# 24V_Conv_Draft.net
KiCad netlist of a schematic drawn in Altium Designer
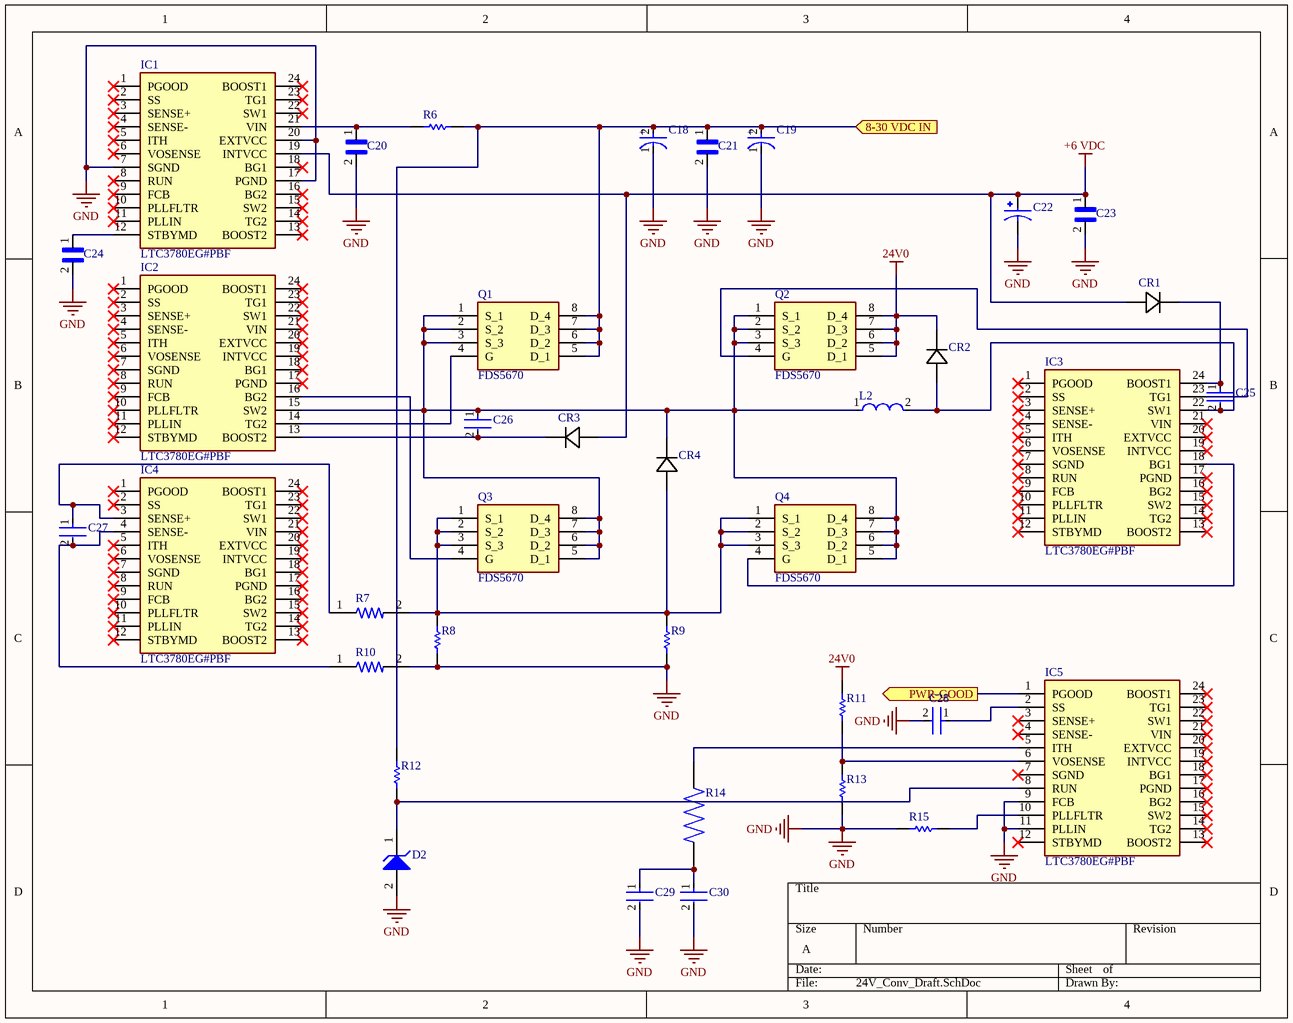
[diagram p0: 24V_Conv_Draft.SchDoc]

(export (version "E")
  (design (tool "Eeschema 10.0.6"))
  (components
    (comp (ref "C18")
      (value "35SVPF22M")
      (footprint "FP-SVPFC6-MFG")
      (description "CAP ALUM POLY 22UF 20% 35V SMD")
      (fields (field (name "TOLERANCE") "20%") (field (name "VOLTAGE") "35V"))
      (libsource (lib "Altium Content Vault") (part "203bc49f2ac43e59fd269a8c329ed05"))
    )
    (comp (ref "C19")
      (value "EEE-HA1E221UP")
      (footprint "FP-HAF-MFG")
      (description "CAP ALUM 220UF 20% 25V SMD")
      (fields
        (field (name "VOLTAGE") "25V")
        (field (name "OCTOPART") "https://octopart.com/eee-ha1e221up-panasonic-39481261")
      )
      (libsource (lib "Altium Content Vault") (part "a00bbbee19879c290e62620ae7e47b1"))
    )
    (comp (ref "C20")
      (value "GRM022R60J104ME15L")
      (footprint "CAPC0402X22N")
      (description "01005 0.1 uF 6.3 V Â±20% Tolerance X5R SMT Multilayer Ceramic Capacitor")
      (fields (field (name "MF") "Murata Electronics"))
      (libsource (lib "0.1uF_Cap_GRM022R60J104ME15L") (part "GRM022R60J104ME15L"))
    )
    (comp (ref "C21")
      (value "GRM022R60J104ME15L")
      (footprint "CAPC0402X22N")
      (description "01005 0.1 uF 6.3 V Â±20% Tolerance X5R SMT Multilayer Ceramic Capacitor")
      (fields (field (name "MF") "Murata Electronics"))
      (libsource (lib "0.1uF_Cap_GRM022R60J104ME15L") (part "GRM022R60J104ME15L"))
    )
    (comp (ref "C22")
      (value "EEVEB2V4R7Q")
      (footprint "CAP_EEVEB2V4R7Q")
      (description "CAP ALUM 4.7UF 20% 350V SMD")
      (fields (field (name "MF") "Panasonic Electronic Components") (field (name "MP") "EEV-EB2V4R7Q"))
      (libsource (lib "4.7uF_Pol_Cap_EEVEB2V4R7Q") (part "EEVEB2V4R7Q"))
    )
    (comp (ref "C23")
      (value "GRM022R60J104ME15L")
      (footprint "CAPC0402X22N")
      (description "01005 0.1 uF 6.3 V Â±20% Tolerance X5R SMT Multilayer Ceramic Capacitor")
      (fields (field (name "MF") "Murata Electronics"))
      (libsource (lib "0.1uF_Cap_GRM022R60J104ME15L") (part "GRM022R60J104ME15L"))
    )
    (comp (ref "C24")
      (value "GRM022R60J104ME15L")
      (footprint "CAPC0402X22N")
      (description "01005 0.1 uF 6.3 V Â±20% Tolerance X5R SMT Multilayer Ceramic Capacitor")
      (fields (field (name "MF") "Murata Electronics"))
      (libsource (lib "0.1uF_Cap_GRM022R60J104ME15L") (part "GRM022R60J104ME15L"))
    )
    (comp (ref "C25")
      (value "C0805C224K5RACTU")
      (footprint "FP-C0805C-DN-IPC_A")
      (description "CAP CER 0.22UF 50V X7R 0805")
      (fields
        (field (name "MANUFACTURER") "KEMET")
        (field (name "OCTOPART") "https://octopart.com/c0805c224k5ractu-kemet-144670")
      )
      (libsource (lib "Altium Content Vault") (part "b4654b650e69147ec39a6b967a45e02"))
    )
    (comp (ref "C26")
      (value "C0805C224K5RACTU")
      (footprint "FP-C0805C-DN-IPC_A")
      (description "CAP CER 0.22UF 50V X7R 0805")
      (fields
        (field (name "MANUFACTURER") "KEMET")
        (field (name "OCTOPART") "https://octopart.com/c0805c224k5ractu-kemet-144670")
      )
      (libsource (lib "Altium Content Vault") (part "b4654b650e69147ec39a6b967a45e02"))
    )
    (comp (ref "C27")
      (value "C1206C680J5GACTU")
      (footprint "FP-C1206C-EB-MFG")
      (description "1206 C 68pF Ceramic Multilayer Capacitor; 50 VDC; +125degC; C0G Dielec; +/-5%")
      (fields
        (field (name "OCTOPART") "https://octopart.com/c1206c680j5gactu-kemet-138975")
        (field (name "TOLERANCE") "0.05")
      )
      (libsource (lib "Altium Content Vault") (part "b4654b650e69147ec39a6b967a45e02"))
    )
    (comp (ref "C28")
      (value "CC0805KRX7R9BB223")
      (footprint "FP-CC0805-0_85-IPC_C")
      (description "CAP CER 0.022UF 50V X7R 0805")
      (fields
        (field (name "OCTOPART") "https://octopart.com/cc0805krx7r9bb223-yageo-39467761")
        (field (name "MANUFACTURER") "Yageo")
      )
      (libsource (lib "Altium Content Vault") (part "11868f565c42a9108669ba33697ecf6"))
    )
    (comp (ref "C29")
      (value "C1206C470J5GACTU")
      (footprint "FP-C1206C-EB-MFG")
      (description "CAP CER 47PF 50V C0G/NP0 1206")
      (fields
        (field (name "TOLERANCE") "0.05")
        (field (name "OCTOPART") "https://octopart.com/c1206c470j5gactu-kemet-96509")
      )
      (libsource (lib "Altium Content Vault") (part "b4654b650e69147ec39a6b967a45e02"))
    )
    (comp (ref "C30")
      (value "CC0603KRX7R9BB103")
      (footprint "FP-CC0603-DA-IPC_B")
      (description "CAP CER 10000PF 50V X7R 0603")
      (fields (field (name "TOLERANCE") "0.1") (field (name "MANUFACTURER") "YAGEO"))
      (libsource (lib "Altium Content Vault") (part "11868f565c42a9108669ba33697ecf6"))
    )
    (comp (ref "CR1")
      (value "SS34-E3/9AT")
      (footprint "CR_3/9AT_VIS")
      (description "No Description Available")
      (fields (field (name "COPYRIGHT") "Copyright (C) 2021 Ultra Librarian. All rights reserved."))
      (libsource (lib "SS34-E3&slash_9AT") (part "SS34-E3/9AT"))
    )
    (comp (ref "CR2")
      (value "SS34-E3/9AT")
      (footprint "CR_3/9AT_VIS")
      (description "No Description Available")
      (fields (field (name "COPYRIGHT") "Copyright (C) 2021 Ultra Librarian. All rights reserved."))
      (libsource (lib "SS34-E3&slash_9AT") (part "SS34-E3/9AT"))
    )
    (comp (ref "CR3")
      (value "SS34-E3/9AT")
      (footprint "CR_3/9AT_VIS")
      (description "No Description Available")
      (fields (field (name "COPYRIGHT") "Copyright (C) 2021 Ultra Librarian. All rights reserved."))
      (libsource (lib "SS34-E3&slash_9AT") (part "SS34-E3/9AT"))
    )
    (comp (ref "CR4")
      (value "SS34-E3/9AT")
      (footprint "CR_3/9AT_VIS")
      (description "No Description Available")
      (fields (field (name "COPYRIGHT") "Copyright (C) 2021 Ultra Librarian. All rights reserved."))
      (libsource (lib "SS34-E3&slash_9AT") (part "SS34-E3/9AT"))
    )
    (comp (ref "D2")
      (value "MMSZ4689T1G")
      (footprint "ONSC-SOD-123-2-425-04_V")
      (description "Zener Voltage Regulator, 500 mW, 2-Pin SOD-123, Pb-Free, Tape and Reel")
      (fields (field (name "MANUFACTURER") "On Semiconductor"))
      (libsource (lib "Altium Content Vault") (part "ONSC-K1A2-2"))
    )
    (comp (ref "IC1")
      (value "LTC3780EG#PBF")
      (footprint "SOP65P780X200-24N")
      (description "Integrated Circuit")
      (fields (field (name "MOUSER PART NUMBER") "584-LTC3780EG#PBF"))
      (libsource (lib "SamacSys") (part "LTC3780EG#PBF"))
    )
    (comp (ref "IC2")
      (value "LTC3780EG#PBF")
      (footprint "SOP65P780X200-24N")
      (description "Integrated Circuit")
      (fields (field (name "MOUSER PART NUMBER") "584-LTC3780EG#PBF"))
      (libsource (lib "SamacSys") (part "LTC3780EG#PBF"))
    )
    (comp (ref "IC3")
      (value "LTC3780EG#PBF")
      (footprint "SOP65P780X200-24N")
      (description "Integrated Circuit")
      (fields (field (name "MOUSER PART NUMBER") "584-LTC3780EG#PBF"))
      (libsource (lib "SamacSys") (part "LTC3780EG#PBF"))
    )
    (comp (ref "IC4")
      (value "LTC3780EG#PBF")
      (footprint "SOP65P780X200-24N")
      (description "Integrated Circuit")
      (fields (field (name "MOUSER PART NUMBER") "584-LTC3780EG#PBF"))
      (libsource (lib "SamacSys") (part "LTC3780EG#PBF"))
    )
    (comp (ref "IC5")
      (value "LTC3780EG#PBF")
      (footprint "SOP65P780X200-24N")
      (description "Integrated Circuit")
      (fields (field (name "MOUSER PART NUMBER") "584-LTC3780EG#PBF"))
      (libsource (lib "SamacSys") (part "LTC3780EG#PBF"))
    )
    (comp (ref "L2")
      (value "IHLP5050CEER4R7M01")
      (footprint "FP-IHLP-5050CE-FP_3_175x3-MFG")
      (description "Commercial Inductors, High Saturation Series 4.7uH 10A 15mΩ 20%")
      (fields (field (name "TOLERANCE") "20%"))
      (libsource (lib "Altium Content Vault") (part "725321dda6339637d4d059423bc1c3c"))
    )
    (comp (ref "Q1")
      (value "FDS5670")
      (footprint "SOIC127P600X175-8N")
      (description "MOSFET (N-Channel)")
      (fields (field (name "MOUSER PART NUMBER") "512-FDS5670"))
      (libsource (lib "SamacSys") (part "FDS5670"))
    )
    (comp (ref "Q2")
      (value "FDS5670")
      (footprint "SOIC127P600X175-8N")
      (description "MOSFET (N-Channel)")
      (fields (field (name "MOUSER PART NUMBER") "512-FDS5670"))
      (libsource (lib "SamacSys") (part "FDS5670"))
    )
    (comp (ref "Q3")
      (value "FDS5670")
      (footprint "SOIC127P600X175-8N")
      (description "MOSFET (N-Channel)")
      (fields (field (name "MOUSER PART NUMBER") "512-FDS5670"))
      (libsource (lib "SamacSys") (part "FDS5670"))
    )
    (comp (ref "Q4")
      (value "FDS5670")
      (footprint "SOIC127P600X175-8N")
      (description "MOSFET (N-Channel)")
      (fields (field (name "MOUSER PART NUMBER") "512-FDS5670"))
      (libsource (lib "SamacSys") (part "FDS5670"))
    )
    (comp (ref "R6")
      (value "ERJ-6ENF10R0V")
      (footprint "RESC2013X70X40NL20T20")
      (fields (field (name "MANUFACTURER") "Panasonic"))
      (libsource (lib "Altium Content Vault") (part "RES"))
    )
    (comp (ref "R7")
      (value "CRGS0805J100R")
      (footprint "RESC2012X65N")
      (description "100 Ohms Â±5% 0.5W, 1/2W Chip Resistor 0805 _2012 Metric_ Pulse Withstanding Thick Film")
      (fields (field (name "MF") "TE Connectivity"))
      (libsource (lib "100_Res_CRGS0805J100R") (part "CRGS0805J100R"))
    )
    (comp (ref "R8")
      (value "ERJ8BWFR018V")
      (footprint "RESC3216X70X50NL05T20")
      (fields (field (name "MANUFACTURER") "Panasonic"))
      (libsource (lib "Altium Content Vault") (part "RES"))
    )
    (comp (ref "R9")
      (value "ERJ8BWFR018V")
      (footprint "RESC3216X70X50NL05T20")
      (fields (field (name "MANUFACTURER") "Panasonic"))
      (libsource (lib "Altium Content Vault") (part "RES"))
    )
    (comp (ref "R10")
      (value "CRGS0805J100R")
      (footprint "RESC2012X65N")
      (description "100 Ohms Â±5% 0.5W, 1/2W Chip Resistor 0805 _2012 Metric_ Pulse Withstanding Thick Film")
      (fields (field (name "MF") "TE Connectivity"))
      (libsource (lib "100_Res_CRGS0805J100R") (part "CRGS0805J100R"))
    )
    (comp (ref "R11")
      (value "CRCW1206294KFKEA")
      (footprint "RESC3216X60X45ML10T20")
      (fields (field (name "MANUFACTURER") "Vishay Dale"))
      (libsource (lib "Altium Content Vault") (part "RES"))
    )
    (comp (ref "R12")
      (value "ERJ3EKF1002V")
      (footprint "RESC1609X55X30LL15T15")
      (description "Chip Resistor, 10 KOhm, +/- 1%, 0.1 W, -55 to 155 degC, 0603 (1608 Metric), RoHS, Tape and Reel")
      (fields (field (name "TOLERANCE") "1%") (field (name "MANUFACTURER") "Panasonic"))
      (libsource (lib "Altium Content Vault") (part "RES-2"))
    )
    (comp (ref "R13")
      (value "ERJ3EKF1002V")
      (footprint "RESC1609X55X30LL15T15")
      (description "Chip Resistor, 10 KOhm, +/- 1%, 0.1 W, -55 to 155 degC, 0603 (1608 Metric), RoHS, Tape and Reel")
      (fields (field (name "TOLERANCE") "1%") (field (name "MANUFACTURER") "Panasonic"))
      (libsource (lib "Altium Content Vault") (part "RES-2"))
    )
    (comp (ref "R14")
      (value "RC1206JR-07100KL")
      (footprint "RESC3116X65N")
      (description "Carbon film resistor 100 kâ„¦ SMD 1206 0.25 W 5 % 200 ppm Yageo RC1206JR-07100KL 1 pc(s)")
      (libsource (lib "100K_Res_RC1206JR-07100KL") (part "RC1206JR-07100KL"))
    )
    (comp (ref "R15")
      (value "ERJ3EKF1002V")
      (footprint "RESC1609X55X30LL15T15")
      (description "Chip Resistor, 10 KOhm, +/- 1%, 0.1 W, -55 to 155 degC, 0603 (1608 Metric), RoHS, Tape and Reel")
      (fields (field (name "TOLERANCE") "1%") (field (name "MANUFACTURER") "Panasonic"))
      (libsource (lib "Altium Content Vault") (part "RES-2"))
    )
  )
  (nets
    (net (code "1") (name "+6 VDC") (class "Default")
      (node (ref "C22") (pin "1") (pinfunction "1_1") (pintype "passive"))
      (node (ref "C23") (pin "1") (pinfunction "1_1") (pintype "passive"))
      (node (ref "CR1") (pin "1") (pinfunction "CATHODE_1") (pintype "passive"))
      (node (ref "CR3") (pin "1") (pinfunction "CATHODE_1") (pintype "passive"))
      (node (ref "IC1") (pin "19") (pinfunction "INTVCC_19") (pintype "passive"))
    )
    (net (code "2") (name "/8-30 VDC IN") (class "Default")
      (node (ref "C18") (pin "2") (pinfunction "A_2") (pintype "passive"))
      (node (ref "C19") (pin "2") (pinfunction "A_2") (pintype "passive"))
      (node (ref "C21") (pin "1") (pinfunction "1_1") (pintype "passive"))
      (node (ref "Q1") (pin "5") (pinfunction "D_1_5") (pintype "passive"))
      (node (ref "Q1") (pin "6") (pinfunction "D_2_6") (pintype "passive"))
      (node (ref "Q1") (pin "7") (pinfunction "D_3_7") (pintype "passive"))
      (node (ref "Q1") (pin "8") (pinfunction "D_4_8") (pintype "passive"))
      (node (ref "R12") (pin "1") (pinfunction "1_1") (pintype "passive"))
      (node (ref "R6") (pin "2") (pinfunction "2_2") (pintype "passive"))
    )
    (net (code "3") (name "/PWR-GOOD") (class "Default")
      (node (ref "IC5") (pin "1") (pinfunction "PGOOD_1") (pintype "passive"))
    )
    (net (code "4") (name "24V0") (class "Default")
      (node (ref "CR2") (pin "2") (pinfunction "ANODE_2") (pintype "passive"))
      (node (ref "Q2") (pin "5") (pinfunction "D_1_5") (pintype "passive"))
      (node (ref "Q2") (pin "6") (pinfunction "D_2_6") (pintype "passive"))
      (node (ref "Q2") (pin "7") (pinfunction "D_3_7") (pintype "passive"))
      (node (ref "Q2") (pin "8") (pinfunction "D_4_8") (pintype "passive"))
      (node (ref "R11") (pin "1") (pinfunction "1_1") (pintype "passive"))
    )
    (net (code "5") (name "GND") (class "Default")
      (node (ref "C18") (pin "1") (pinfunction "C_1") (pintype "passive"))
      (node (ref "C19") (pin "1") (pinfunction "C_1") (pintype "passive"))
      (node (ref "C20") (pin "2") (pinfunction "2_2") (pintype "passive"))
      (node (ref "C21") (pin "2") (pinfunction "2_2") (pintype "passive"))
      (node (ref "C22") (pin "2") (pinfunction "2_2") (pintype "passive"))
      (node (ref "C23") (pin "2") (pinfunction "2_2") (pintype "passive"))
      (node (ref "C24") (pin "2") (pinfunction "2_2") (pintype "passive"))
      (node (ref "C28") (pin "2") (pinfunction "2_2") (pintype "passive"))
      (node (ref "C29") (pin "2") (pinfunction "2_2") (pintype "passive"))
      (node (ref "C30") (pin "2") (pinfunction "2_2") (pintype "passive"))
      (node (ref "D2") (pin "2") (pinfunction "A_2") (pintype "passive"))
      (node (ref "IC1") (pin "17") (pinfunction "PGND_17") (pintype "passive"))
      (node (ref "IC1") (pin "20") (pinfunction "EXTVCC_20") (pintype "passive"))
      (node (ref "IC1") (pin "7") (pinfunction "SGND_7") (pintype "passive"))
      (node (ref "IC5") (pin "11") (pinfunction "PLLIN_11") (pintype "passive"))
      (node (ref "IC5") (pin "9") (pinfunction "FCB_9") (pintype "passive"))
      (node (ref "R10") (pin "2") (pinfunction "2_2") (pintype "passive"))
      (node (ref "R13") (pin "2") (pinfunction "2_2") (pintype "passive"))
      (node (ref "R15") (pin "2") (pinfunction "2_2") (pintype "passive"))
      (node (ref "R8") (pin "2") (pinfunction "2_2") (pintype "passive"))
      (node (ref "R9") (pin "2") (pinfunction "2_2") (pintype "passive"))
    )
    (net (code "6") (name "Net-(C29-Pad1)") (class "Default")
      (node (ref "C29") (pin "1") (pinfunction "1_1") (pintype "passive"))
      (node (ref "C30") (pin "1") (pinfunction "1_1") (pintype "passive"))
      (node (ref "R14") (pin "2") (pinfunction "2_2") (pintype "passive"))
    )
    (net (code "7") (name "Net-(CR1-ANODE)") (class "Default")
      (node (ref "C25") (pin "1") (pinfunction "1_1") (pintype "passive"))
      (node (ref "CR1") (pin "2") (pinfunction "ANODE_2") (pintype "passive"))
      (node (ref "IC3") (pin "24") (pinfunction "BOOST1_24") (pintype "passive"))
    )
    (net (code "8") (name "Net-(CR2-CATHODE)") (class "Default")
      (node (ref "C25") (pin "2") (pinfunction "2_2") (pintype "passive"))
      (node (ref "CR2") (pin "1") (pinfunction "CATHODE_1") (pintype "passive"))
      (node (ref "IC3") (pin "22") (pinfunction "SW1_22") (pintype "passive"))
      (node (ref "L2") (pin "2") (pinfunction "2_2") (pintype "passive"))
    )
    (net (code "9") (name "Net-(CR3-ANODE)") (class "Default")
      (node (ref "C26") (pin "2") (pinfunction "2_2") (pintype "passive"))
      (node (ref "CR3") (pin "2") (pinfunction "ANODE_2") (pintype "passive"))
      (node (ref "IC2") (pin "13") (pinfunction "BOOST2_13") (pintype "passive"))
    )
    (net (code "10") (name "Net-(CR4-ANODE)") (class "Default")
      (node (ref "C26") (pin "1") (pinfunction "1_1") (pintype "passive"))
      (node (ref "CR4") (pin "2") (pinfunction "ANODE_2") (pintype "passive"))
      (node (ref "IC2") (pin "15") (pinfunction "SW2_15") (pintype "passive"))
      (node (ref "L2") (pin "1") (pinfunction "1_1") (pintype "passive"))
      (node (ref "Q1") (pin "1") (pinfunction "S_1_1") (pintype "passive"))
      (node (ref "Q1") (pin "2") (pinfunction "S_2_2") (pintype "passive"))
      (node (ref "Q1") (pin "3") (pinfunction "S_3_3") (pintype "passive"))
      (node (ref "Q2") (pin "1") (pinfunction "S_1_1") (pintype "passive"))
      (node (ref "Q2") (pin "2") (pinfunction "S_2_2") (pintype "passive"))
      (node (ref "Q2") (pin "3") (pinfunction "S_3_3") (pintype "passive"))
      (node (ref "Q3") (pin "5") (pinfunction "D_1_5") (pintype "passive"))
      (node (ref "Q3") (pin "6") (pinfunction "D_2_6") (pintype "passive"))
      (node (ref "Q3") (pin "7") (pinfunction "D_3_7") (pintype "passive"))
      (node (ref "Q3") (pin "8") (pinfunction "D_4_8") (pintype "passive"))
      (node (ref "Q4") (pin "5") (pinfunction "D_1_5") (pintype "passive"))
      (node (ref "Q4") (pin "6") (pinfunction "D_2_6") (pintype "passive"))
      (node (ref "Q4") (pin "7") (pinfunction "D_3_7") (pintype "passive"))
      (node (ref "Q4") (pin "8") (pinfunction "D_4_8") (pintype "passive"))
    )
    (net (code "11") (name "Net-(CR4-CATHODE)") (class "Default")
      (node (ref "CR4") (pin "1") (pinfunction "CATHODE_1") (pintype "passive"))
      (node (ref "Q3") (pin "1") (pinfunction "S_1_1") (pintype "passive"))
      (node (ref "Q3") (pin "2") (pinfunction "S_2_2") (pintype "passive"))
      (node (ref "Q3") (pin "3") (pinfunction "S_3_3") (pintype "passive"))
      (node (ref "Q4") (pin "1") (pinfunction "S_1_1") (pintype "passive"))
      (node (ref "Q4") (pin "2") (pinfunction "S_2_2") (pintype "passive"))
      (node (ref "Q4") (pin "3") (pinfunction "S_3_3") (pintype "passive"))
      (node (ref "R7") (pin "2") (pinfunction "2_2") (pintype "passive"))
      (node (ref "R8") (pin "1") (pinfunction "1_1") (pintype "passive"))
      (node (ref "R9") (pin "1") (pinfunction "1_1") (pintype "passive"))
    )
    (net (code "12") (name "Net-(D2-K)") (class "Default")
      (node (ref "D2") (pin "1") (pinfunction "K_1") (pintype "passive"))
      (node (ref "IC5") (pin "8") (pinfunction "RUN_8") (pintype "passive"))
      (node (ref "R12") (pin "2") (pinfunction "2_2") (pintype "passive"))
    )
    (net (code "13") (name "Net-(IC1-STBYMD)") (class "Default")
      (node (ref "C24") (pin "1") (pinfunction "1_1") (pintype "passive"))
      (node (ref "IC1") (pin "12") (pinfunction "STBYMD_12") (pintype "passive"))
    )
    (net (code "14") (name "Net-(IC1-VIN)") (class "Default")
      (node (ref "C20") (pin "1") (pinfunction "1_1") (pintype "passive"))
      (node (ref "IC1") (pin "21") (pinfunction "VIN_21") (pintype "passive"))
      (node (ref "R6") (pin "1") (pinfunction "1_1") (pintype "passive"))
    )
    (net (code "15") (name "Net-(IC2-BG2)") (class "Default")
      (node (ref "IC2") (pin "16") (pinfunction "BG2_16") (pintype "passive"))
      (node (ref "Q3") (pin "4") (pinfunction "G_4") (pintype "passive"))
    )
    (net (code "16") (name "Net-(IC2-TG2)") (class "Default")
      (node (ref "IC2") (pin "14") (pinfunction "TG2_14") (pintype "passive"))
      (node (ref "Q1") (pin "4") (pinfunction "G_4") (pintype "passive"))
    )
    (net (code "17") (name "Net-(IC3-BG1)") (class "Default")
      (node (ref "IC3") (pin "18") (pinfunction "BG1_18") (pintype "passive"))
      (node (ref "Q4") (pin "4") (pinfunction "G_4") (pintype "passive"))
    )
    (net (code "18") (name "Net-(IC3-TG1)") (class "Default")
      (node (ref "IC3") (pin "23") (pinfunction "TG1_23") (pintype "passive"))
      (node (ref "Q2") (pin "4") (pinfunction "G_4") (pintype "passive"))
    )
    (net (code "19") (name "Net-(IC4-SENSE+)") (class "Default")
      (node (ref "C27") (pin "1") (pinfunction "1_1") (pintype "passive"))
      (node (ref "IC4") (pin "3") (pinfunction "SENSE+_3") (pintype "passive"))
      (node (ref "R7") (pin "1") (pinfunction "1_1") (pintype "passive"))
    )
    (net (code "20") (name "Net-(IC4-SENSE-)") (class "Default")
      (node (ref "C27") (pin "2") (pinfunction "2_2") (pintype "passive"))
      (node (ref "IC4") (pin "4") (pinfunction "SENSE-_4") (pintype "passive"))
      (node (ref "R10") (pin "1") (pinfunction "1_1") (pintype "passive"))
    )
    (net (code "21") (name "Net-(IC5-ITH)") (class "Default")
      (node (ref "IC5") (pin "5") (pinfunction "ITH_5") (pintype "passive"))
      (node (ref "R14") (pin "1") (pinfunction "1_1") (pintype "passive"))
    )
    (net (code "22") (name "Net-(IC5-PLLFLTR)") (class "Default")
      (node (ref "IC5") (pin "10") (pinfunction "PLLFLTR_10") (pintype "passive"))
      (node (ref "R15") (pin "1") (pinfunction "1_1") (pintype "passive"))
    )
    (net (code "23") (name "Net-(IC5-SS)") (class "Default")
      (node (ref "C28") (pin "1") (pinfunction "1_1") (pintype "passive"))
      (node (ref "IC5") (pin "2") (pinfunction "SS_2") (pintype "passive"))
    )
    (net (code "24") (name "Net-(IC5-VOSENSE)") (class "Default")
      (node (ref "IC5") (pin "6") (pinfunction "VOSENSE_6") (pintype "passive"))
      (node (ref "R11") (pin "2") (pinfunction "2_2") (pintype "passive"))
      (node (ref "R13") (pin "1") (pinfunction "1_1") (pintype "passive"))
    )
    (net (code "25") (name "unconnected-(IC1-BG1-Pad18)") (class "Default")
      (node (ref "IC1") (pin "18") (pinfunction "BG1_18") (pintype "passive+no_connect"))
    )
    (net (code "26") (name "unconnected-(IC1-BG2-Pad16)") (class "Default")
      (node (ref "IC1") (pin "16") (pinfunction "BG2_16") (pintype "passive+no_connect"))
    )
    (net (code "27") (name "unconnected-(IC1-BOOST1-Pad24)") (class "Default")
      (node (ref "IC1") (pin "24") (pinfunction "BOOST1_24") (pintype "passive+no_connect"))
    )
    (net (code "28") (name "unconnected-(IC1-BOOST2-Pad13)") (class "Default")
      (node (ref "IC1") (pin "13") (pinfunction "BOOST2_13") (pintype "passive+no_connect"))
    )
    (net (code "29") (name "unconnected-(IC1-FCB-Pad9)") (class "Default")
      (node (ref "IC1") (pin "9") (pinfunction "FCB_9") (pintype "passive+no_connect"))
    )
    (net (code "30") (name "unconnected-(IC1-ITH-Pad5)") (class "Default")
      (node (ref "IC1") (pin "5") (pinfunction "ITH_5") (pintype "passive+no_connect"))
    )
    (net (code "31") (name "unconnected-(IC1-PGOOD-Pad1)") (class "Default")
      (node (ref "IC1") (pin "1") (pinfunction "PGOOD_1") (pintype "passive+no_connect"))
    )
    (net (code "32") (name "unconnected-(IC1-PLLFLTR-Pad10)") (class "Default")
      (node (ref "IC1") (pin "10") (pinfunction "PLLFLTR_10") (pintype "passive+no_connect"))
    )
    (net (code "33") (name "unconnected-(IC1-PLLIN-Pad11)") (class "Default")
      (node (ref "IC1") (pin "11") (pinfunction "PLLIN_11") (pintype "passive+no_connect"))
    )
    (net (code "34") (name "unconnected-(IC1-RUN-Pad8)") (class "Default")
      (node (ref "IC1") (pin "8") (pinfunction "RUN_8") (pintype "passive+no_connect"))
    )
    (net (code "35") (name "unconnected-(IC1-SENSE+-Pad3)") (class "Default")
      (node (ref "IC1") (pin "3") (pinfunction "SENSE+_3") (pintype "passive+no_connect"))
    )
    (net (code "36") (name "unconnected-(IC1-SENSE--Pad4)") (class "Default")
      (node (ref "IC1") (pin "4") (pinfunction "SENSE-_4") (pintype "passive+no_connect"))
    )
    (net (code "37") (name "unconnected-(IC1-SS-Pad2)") (class "Default")
      (node (ref "IC1") (pin "2") (pinfunction "SS_2") (pintype "passive+no_connect"))
    )
    (net (code "38") (name "unconnected-(IC1-SW1-Pad22)") (class "Default")
      (node (ref "IC1") (pin "22") (pinfunction "SW1_22") (pintype "passive+no_connect"))
    )
    (net (code "39") (name "unconnected-(IC1-SW2-Pad15)") (class "Default")
      (node (ref "IC1") (pin "15") (pinfunction "SW2_15") (pintype "passive+no_connect"))
    )
    (net (code "40") (name "unconnected-(IC1-TG1-Pad23)") (class "Default")
      (node (ref "IC1") (pin "23") (pinfunction "TG1_23") (pintype "passive+no_connect"))
    )
    (net (code "41") (name "unconnected-(IC1-TG2-Pad14)") (class "Default")
      (node (ref "IC1") (pin "14") (pinfunction "TG2_14") (pintype "passive+no_connect"))
    )
    (net (code "42") (name "unconnected-(IC1-VOSENSE-Pad6)") (class "Default")
      (node (ref "IC1") (pin "6") (pinfunction "VOSENSE_6") (pintype "passive+no_connect"))
    )
    (net (code "43") (name "unconnected-(IC2-BG1-Pad18)") (class "Default")
      (node (ref "IC2") (pin "18") (pinfunction "BG1_18") (pintype "passive+no_connect"))
    )
    (net (code "44") (name "unconnected-(IC2-BOOST1-Pad24)") (class "Default")
      (node (ref "IC2") (pin "24") (pinfunction "BOOST1_24") (pintype "passive+no_connect"))
    )
    (net (code "45") (name "unconnected-(IC2-EXTVCC-Pad20)") (class "Default")
      (node (ref "IC2") (pin "20") (pinfunction "EXTVCC_20") (pintype "passive+no_connect"))
    )
    (net (code "46") (name "unconnected-(IC2-FCB-Pad9)") (class "Default")
      (node (ref "IC2") (pin "9") (pinfunction "FCB_9") (pintype "passive+no_connect"))
    )
    (net (code "47") (name "unconnected-(IC2-INTVCC-Pad19)") (class "Default")
      (node (ref "IC2") (pin "19") (pinfunction "INTVCC_19") (pintype "passive+no_connect"))
    )
    (net (code "48") (name "unconnected-(IC2-ITH-Pad5)") (class "Default")
      (node (ref "IC2") (pin "5") (pinfunction "ITH_5") (pintype "passive+no_connect"))
    )
    (net (code "49") (name "unconnected-(IC2-PGND-Pad17)") (class "Default")
      (node (ref "IC2") (pin "17") (pinfunction "PGND_17") (pintype "passive+no_connect"))
    )
    (net (code "50") (name "unconnected-(IC2-PGOOD-Pad1)") (class "Default")
      (node (ref "IC2") (pin "1") (pinfunction "PGOOD_1") (pintype "passive+no_connect"))
    )
    (net (code "51") (name "unconnected-(IC2-PLLFLTR-Pad10)") (class "Default")
      (node (ref "IC2") (pin "10") (pinfunction "PLLFLTR_10") (pintype "passive+no_connect"))
    )
    (net (code "52") (name "unconnected-(IC2-PLLIN-Pad11)") (class "Default")
      (node (ref "IC2") (pin "11") (pinfunction "PLLIN_11") (pintype "passive+no_connect"))
    )
    (net (code "53") (name "unconnected-(IC2-RUN-Pad8)") (class "Default")
      (node (ref "IC2") (pin "8") (pinfunction "RUN_8") (pintype "passive+no_connect"))
    )
    (net (code "54") (name "unconnected-(IC2-SENSE+-Pad3)") (class "Default")
      (node (ref "IC2") (pin "3") (pinfunction "SENSE+_3") (pintype "passive+no_connect"))
    )
    (net (code "55") (name "unconnected-(IC2-SENSE--Pad4)") (class "Default")
      (node (ref "IC2") (pin "4") (pinfunction "SENSE-_4") (pintype "passive+no_connect"))
    )
    (net (code "56") (name "unconnected-(IC2-SGND-Pad7)") (class "Default")
      (node (ref "IC2") (pin "7") (pinfunction "SGND_7") (pintype "passive+no_connect"))
    )
    (net (code "57") (name "unconnected-(IC2-SS-Pad2)") (class "Default")
      (node (ref "IC2") (pin "2") (pinfunction "SS_2") (pintype "passive+no_connect"))
    )
    (net (code "58") (name "unconnected-(IC2-STBYMD-Pad12)") (class "Default")
      (node (ref "IC2") (pin "12") (pinfunction "STBYMD_12") (pintype "passive+no_connect"))
    )
    (net (code "59") (name "unconnected-(IC2-SW1-Pad22)") (class "Default")
      (node (ref "IC2") (pin "22") (pinfunction "SW1_22") (pintype "passive+no_connect"))
    )
    (net (code "60") (name "unconnected-(IC2-TG1-Pad23)") (class "Default")
      (node (ref "IC2") (pin "23") (pinfunction "TG1_23") (pintype "passive+no_connect"))
    )
    (net (code "61") (name "unconnected-(IC2-VIN-Pad21)") (class "Default")
      (node (ref "IC2") (pin "21") (pinfunction "VIN_21") (pintype "passive+no_connect"))
    )
    (net (code "62") (name "unconnected-(IC2-VOSENSE-Pad6)") (class "Default")
      (node (ref "IC2") (pin "6") (pinfunction "VOSENSE_6") (pintype "passive+no_connect"))
    )
    (net (code "63") (name "unconnected-(IC3-BG2-Pad16)") (class "Default")
      (node (ref "IC3") (pin "16") (pinfunction "BG2_16") (pintype "passive+no_connect"))
    )
    (net (code "64") (name "unconnected-(IC3-BOOST2-Pad13)") (class "Default")
      (node (ref "IC3") (pin "13") (pinfunction "BOOST2_13") (pintype "passive+no_connect"))
    )
    (net (code "65") (name "unconnected-(IC3-EXTVCC-Pad20)") (class "Default")
      (node (ref "IC3") (pin "20") (pinfunction "EXTVCC_20") (pintype "passive+no_connect"))
    )
    (net (code "66") (name "unconnected-(IC3-FCB-Pad9)") (class "Default")
      (node (ref "IC3") (pin "9") (pinfunction "FCB_9") (pintype "passive+no_connect"))
    )
    (net (code "67") (name "unconnected-(IC3-INTVCC-Pad19)") (class "Default")
      (node (ref "IC3") (pin "19") (pinfunction "INTVCC_19") (pintype "passive+no_connect"))
    )
    (net (code "68") (name "unconnected-(IC3-ITH-Pad5)") (class "Default")
      (node (ref "IC3") (pin "5") (pinfunction "ITH_5") (pintype "passive+no_connect"))
    )
    (net (code "69") (name "unconnected-(IC3-PGND-Pad17)") (class "Default")
      (node (ref "IC3") (pin "17") (pinfunction "PGND_17") (pintype "passive+no_connect"))
    )
    (net (code "70") (name "unconnected-(IC3-PGOOD-Pad1)") (class "Default")
      (node (ref "IC3") (pin "1") (pinfunction "PGOOD_1") (pintype "passive+no_connect"))
    )
    (net (code "71") (name "unconnected-(IC3-PLLFLTR-Pad10)") (class "Default")
      (node (ref "IC3") (pin "10") (pinfunction "PLLFLTR_10") (pintype "passive+no_connect"))
    )
    (net (code "72") (name "unconnected-(IC3-PLLIN-Pad11)") (class "Default")
      (node (ref "IC3") (pin "11") (pinfunction "PLLIN_11") (pintype "passive+no_connect"))
    )
    (net (code "73") (name "unconnected-(IC3-RUN-Pad8)") (class "Default")
      (node (ref "IC3") (pin "8") (pinfunction "RUN_8") (pintype "passive+no_connect"))
    )
    (net (code "74") (name "unconnected-(IC3-SENSE+-Pad3)") (class "Default")
      (node (ref "IC3") (pin "3") (pinfunction "SENSE+_3") (pintype "passive+no_connect"))
    )
    (net (code "75") (name "unconnected-(IC3-SENSE--Pad4)") (class "Default")
      (node (ref "IC3") (pin "4") (pinfunction "SENSE-_4") (pintype "passive+no_connect"))
    )
    (net (code "76") (name "unconnected-(IC3-SGND-Pad7)") (class "Default")
      (node (ref "IC3") (pin "7") (pinfunction "SGND_7") (pintype "passive+no_connect"))
    )
    (net (code "77") (name "unconnected-(IC3-SS-Pad2)") (class "Default")
      (node (ref "IC3") (pin "2") (pinfunction "SS_2") (pintype "passive+no_connect"))
    )
    (net (code "78") (name "unconnected-(IC3-STBYMD-Pad12)") (class "Default")
      (node (ref "IC3") (pin "12") (pinfunction "STBYMD_12") (pintype "passive+no_connect"))
    )
    (net (code "79") (name "unconnected-(IC3-SW2-Pad15)") (class "Default")
      (node (ref "IC3") (pin "15") (pinfunction "SW2_15") (pintype "passive+no_connect"))
    )
    (net (code "80") (name "unconnected-(IC3-TG2-Pad14)") (class "Default")
      (node (ref "IC3") (pin "14") (pinfunction "TG2_14") (pintype "passive+no_connect"))
    )
    (net (code "81") (name "unconnected-(IC3-VIN-Pad21)") (class "Default")
      (node (ref "IC3") (pin "21") (pinfunction "VIN_21") (pintype "passive+no_connect"))
    )
    (net (code "82") (name "unconnected-(IC3-VOSENSE-Pad6)") (class "Default")
      (node (ref "IC3") (pin "6") (pinfunction "VOSENSE_6") (pintype "passive+no_connect"))
    )
    (net (code "83") (name "unconnected-(IC4-BG1-Pad18)") (class "Default")
      (node (ref "IC4") (pin "18") (pinfunction "BG1_18") (pintype "passive+no_connect"))
    )
    (net (code "84") (name "unconnected-(IC4-BG2-Pad16)") (class "Default")
      (node (ref "IC4") (pin "16") (pinfunction "BG2_16") (pintype "passive+no_connect"))
    )
    (net (code "85") (name "unconnected-(IC4-BOOST1-Pad24)") (class "Default")
      (node (ref "IC4") (pin "24") (pinfunction "BOOST1_24") (pintype "passive+no_connect"))
    )
    (net (code "86") (name "unconnected-(IC4-BOOST2-Pad13)") (class "Default")
      (node (ref "IC4") (pin "13") (pinfunction "BOOST2_13") (pintype "passive+no_connect"))
    )
    (net (code "87") (name "unconnected-(IC4-EXTVCC-Pad20)") (class "Default")
      (node (ref "IC4") (pin "20") (pinfunction "EXTVCC_20") (pintype "passive+no_connect"))
    )
    (net (code "88") (name "unconnected-(IC4-FCB-Pad9)") (class "Default")
      (node (ref "IC4") (pin "9") (pinfunction "FCB_9") (pintype "passive+no_connect"))
    )
    (net (code "89") (name "unconnected-(IC4-INTVCC-Pad19)") (class "Default")
      (node (ref "IC4") (pin "19") (pinfunction "INTVCC_19") (pintype "passive+no_connect"))
    )
    (net (code "90") (name "unconnected-(IC4-ITH-Pad5)") (class "Default")
      (node (ref "IC4") (pin "5") (pinfunction "ITH_5") (pintype "passive+no_connect"))
    )
    (net (code "91") (name "unconnected-(IC4-PGND-Pad17)") (class "Default")
      (node (ref "IC4") (pin "17") (pinfunction "PGND_17") (pintype "passive+no_connect"))
    )
    (net (code "92") (name "unconnected-(IC4-PGOOD-Pad1)") (class "Default")
      (node (ref "IC4") (pin "1") (pinfunction "PGOOD_1") (pintype "passive+no_connect"))
    )
    (net (code "93") (name "unconnected-(IC4-PLLFLTR-Pad10)") (class "Default")
      (node (ref "IC4") (pin "10") (pinfunction "PLLFLTR_10") (pintype "passive+no_connect"))
    )
    (net (code "94") (name "unconnected-(IC4-PLLIN-Pad11)") (class "Default")
      (node (ref "IC4") (pin "11") (pinfunction "PLLIN_11") (pintype "passive+no_connect"))
    )
    (net (code "95") (name "unconnected-(IC4-RUN-Pad8)") (class "Default")
      (node (ref "IC4") (pin "8") (pinfunction "RUN_8") (pintype "passive+no_connect"))
    )
    (net (code "96") (name "unconnected-(IC4-SGND-Pad7)") (class "Default")
      (node (ref "IC4") (pin "7") (pinfunction "SGND_7") (pintype "passive+no_connect"))
    )
    (net (code "97") (name "unconnected-(IC4-SS-Pad2)") (class "Default")
      (node (ref "IC4") (pin "2") (pinfunction "SS_2") (pintype "passive+no_connect"))
    )
    (net (code "98") (name "unconnected-(IC4-STBYMD-Pad12)") (class "Default")
      (node (ref "IC4") (pin "12") (pinfunction "STBYMD_12") (pintype "passive+no_connect"))
    )
    (net (code "99") (name "unconnected-(IC4-SW1-Pad22)") (class "Default")
      (node (ref "IC4") (pin "22") (pinfunction "SW1_22") (pintype "passive+no_connect"))
    )
    (net (code "100") (name "unconnected-(IC4-SW2-Pad15)") (class "Default")
      (node (ref "IC4") (pin "15") (pinfunction "SW2_15") (pintype "passive+no_connect"))
    )
    (net (code "101") (name "unconnected-(IC4-TG1-Pad23)") (class "Default")
      (node (ref "IC4") (pin "23") (pinfunction "TG1_23") (pintype "passive+no_connect"))
    )
    (net (code "102") (name "unconnected-(IC4-TG2-Pad14)") (class "Default")
      (node (ref "IC4") (pin "14") (pinfunction "TG2_14") (pintype "passive+no_connect"))
    )
    (net (code "103") (name "unconnected-(IC4-VIN-Pad21)") (class "Default")
      (node (ref "IC4") (pin "21") (pinfunction "VIN_21") (pintype "passive+no_connect"))
    )
    (net (code "104") (name "unconnected-(IC4-VOSENSE-Pad6)") (class "Default")
      (node (ref "IC4") (pin "6") (pinfunction "VOSENSE_6") (pintype "passive+no_connect"))
    )
    (net (code "105") (name "unconnected-(IC5-BG1-Pad18)") (class "Default")
      (node (ref "IC5") (pin "18") (pinfunction "BG1_18") (pintype "passive+no_connect"))
    )
    (net (code "106") (name "unconnected-(IC5-BG2-Pad16)") (class "Default")
      (node (ref "IC5") (pin "16") (pinfunction "BG2_16") (pintype "passive+no_connect"))
    )
    (net (code "107") (name "unconnected-(IC5-BOOST1-Pad24)") (class "Default")
      (node (ref "IC5") (pin "24") (pinfunction "BOOST1_24") (pintype "passive+no_connect"))
    )
    (net (code "108") (name "unconnected-(IC5-BOOST2-Pad13)") (class "Default")
      (node (ref "IC5") (pin "13") (pinfunction "BOOST2_13") (pintype "passive+no_connect"))
    )
    (net (code "109") (name "unconnected-(IC5-EXTVCC-Pad20)") (class "Default")
      (node (ref "IC5") (pin "20") (pinfunction "EXTVCC_20") (pintype "passive+no_connect"))
    )
    (net (code "110") (name "unconnected-(IC5-INTVCC-Pad19)") (class "Default")
      (node (ref "IC5") (pin "19") (pinfunction "INTVCC_19") (pintype "passive+no_connect"))
    )
    (net (code "111") (name "unconnected-(IC5-PGND-Pad17)") (class "Default")
      (node (ref "IC5") (pin "17") (pinfunction "PGND_17") (pintype "passive+no_connect"))
    )
    (net (code "112") (name "unconnected-(IC5-SENSE+-Pad3)") (class "Default")
      (node (ref "IC5") (pin "3") (pinfunction "SENSE+_3") (pintype "passive+no_connect"))
    )
    (net (code "113") (name "unconnected-(IC5-SENSE--Pad4)") (class "Default")
      (node (ref "IC5") (pin "4") (pinfunction "SENSE-_4") (pintype "passive+no_connect"))
    )
    (net (code "114") (name "unconnected-(IC5-SGND-Pad7)") (class "Default")
      (node (ref "IC5") (pin "7") (pinfunction "SGND_7") (pintype "passive+no_connect"))
    )
    (net (code "115") (name "unconnected-(IC5-STBYMD-Pad12)") (class "Default")
      (node (ref "IC5") (pin "12") (pinfunction "STBYMD_12") (pintype "passive+no_connect"))
    )
    (net (code "116") (name "unconnected-(IC5-SW1-Pad22)") (class "Default")
      (node (ref "IC5") (pin "22") (pinfunction "SW1_22") (pintype "passive+no_connect"))
    )
    (net (code "117") (name "unconnected-(IC5-SW2-Pad15)") (class "Default")
      (node (ref "IC5") (pin "15") (pinfunction "SW2_15") (pintype "passive+no_connect"))
    )
    (net (code "118") (name "unconnected-(IC5-TG1-Pad23)") (class "Default")
      (node (ref "IC5") (pin "23") (pinfunction "TG1_23") (pintype "passive+no_connect"))
    )
    (net (code "119") (name "unconnected-(IC5-TG2-Pad14)") (class "Default")
      (node (ref "IC5") (pin "14") (pinfunction "TG2_14") (pintype "passive+no_connect"))
    )
    (net (code "120") (name "unconnected-(IC5-VIN-Pad21)") (class "Default")
      (node (ref "IC5") (pin "21") (pinfunction "VIN_21") (pintype "passive+no_connect"))
    )
  )
)
